# fire_alarm.net
KiCad netlist of a schematic drawn in EAGLE
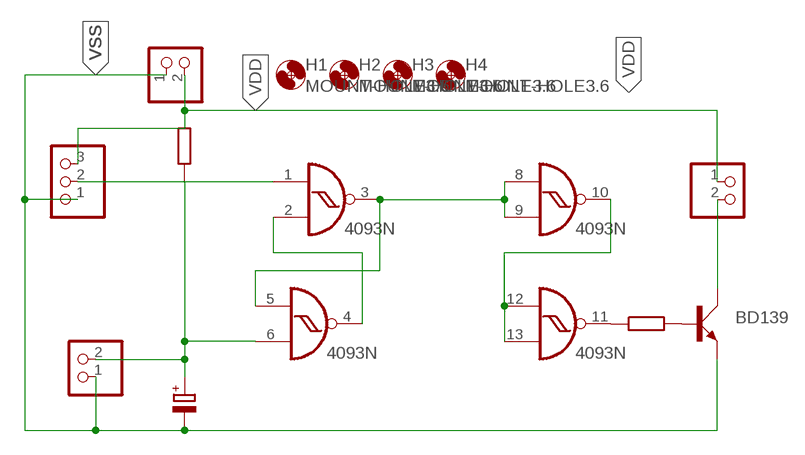
[diagram p0: schematic, sheet 1]

(export (version "E")
  (design (tool "Eeschema 10.0.6"))
  (components
    (comp (ref "C1")
      (value "CPOL-EUE2.5-5")
      (footprint "eagle-import:E2,5-5")
      (libsource (lib "eagle-import") (part "CPOL-EUE2.5-5"))
    )
    (comp (ref "H1")
      (value "MOUNT-HOLE3.6")
      (footprint "eagle-import:3,6")
      (libsource (lib "eagle-import") (part "MOUNT-HOLE3.6"))
    )
    (comp (ref "H2")
      (value "MOUNT-HOLE3.6")
      (footprint "eagle-import:3,6")
      (libsource (lib "eagle-import") (part "MOUNT-HOLE3.6"))
    )
    (comp (ref "H3")
      (value "MOUNT-HOLE3.6")
      (footprint "eagle-import:3,6")
      (libsource (lib "eagle-import") (part "MOUNT-HOLE3.6"))
    )
    (comp (ref "H4")
      (value "MOUNT-HOLE3.6")
      (footprint "eagle-import:3,6")
      (libsource (lib "eagle-import") (part "MOUNT-HOLE3.6"))
    )
    (comp (ref "IC1")
      (value "4093N")
      (footprint "eagle-import:DIL14")
      (libsource (lib "eagle-import") (part "4093N"))
    )
    (comp (ref "JP1")
      (value "PINHD-1X2")
      (footprint "eagle-import:1X02")
      (libsource (lib "eagle-import") (part "PINHD-1X2"))
    )
    (comp (ref "JP2")
      (value "PINHD-1X2")
      (footprint "eagle-import:1X02")
      (libsource (lib "eagle-import") (part "PINHD-1X2"))
    )
    (comp (ref "JP3")
      (value "PINHD-1X2")
      (footprint "eagle-import:1X02")
      (libsource (lib "eagle-import") (part "PINHD-1X2"))
    )
    (comp (ref "JP4")
      (value "PINHD-1X3")
      (footprint "eagle-import:1X03")
      (libsource (lib "eagle-import") (part "PINHD-1X3"))
    )
    (comp (ref "Q1")
      (value "BD139")
      (footprint "eagle-import:TO126AV")
      (libsource (lib "eagle-import") (part "BD139"))
    )
    (comp (ref "R1")
      (value "R-EU_0207/15")
      (footprint "eagle-import:0207_15")
      (libsource (lib "eagle-import") (part "R-EU_0207/15"))
    )
    (comp (ref "R2")
      (value "R-EU_0207/15")
      (footprint "eagle-import:0207_15")
      (libsource (lib "eagle-import") (part "R-EU_0207/15"))
    )
  )
  (nets
    (net (code "1") (name "Net-(IC1A-I0)") (class "Default")
      (node (ref "IC1") (pin "1") (pinfunction "I0_1") (pintype "input"))
      (node (ref "JP4") (pin "2") (pinfunction "2_2") (pintype "passive"))
    )
    (net (code "2") (name "Net-(IC1A-I1)") (class "Default")
      (node (ref "IC1") (pin "2") (pinfunction "I1_2") (pintype "input"))
      (node (ref "IC1") (pin "4") (pinfunction "O_4") (pintype "output"))
    )
    (net (code "3") (name "Net-(IC1A-O)") (class "Default")
      (node (ref "IC1") (pin "3") (pinfunction "O_3") (pintype "output"))
      (node (ref "IC1") (pin "5") (pinfunction "I0_5") (pintype "input"))
      (node (ref "IC1") (pin "8") (pinfunction "I0_8") (pintype "input"))
      (node (ref "IC1") (pin "9") (pinfunction "I1_9") (pintype "input"))
    )
    (net (code "4") (name "Net-(IC1B-I1)") (class "Default")
      (node (ref "C1") (pin "+") (pinfunction "+_+") (pintype "passive"))
      (node (ref "IC1") (pin "6") (pinfunction "I1_6") (pintype "input"))
      (node (ref "JP2") (pin "2") (pinfunction "2_2") (pintype "passive"))
      (node (ref "R2") (pin "1") (pinfunction "1_1") (pintype "passive"))
    )
    (net (code "5") (name "Net-(IC1C-O)") (class "Default")
      (node (ref "IC1") (pin "10") (pinfunction "O_10") (pintype "output"))
      (node (ref "IC1") (pin "12") (pinfunction "I0_12") (pintype "input"))
      (node (ref "IC1") (pin "13") (pinfunction "I1_13") (pintype "input"))
    )
    (net (code "6") (name "Net-(IC1D-O)") (class "Default")
      (node (ref "IC1") (pin "11") (pinfunction "O_11") (pintype "output"))
      (node (ref "R1") (pin "1") (pinfunction "1_1") (pintype "passive"))
    )
    (net (code "7") (name "Net-(JP3-Pad2)") (class "Default")
      (node (ref "JP3") (pin "2") (pinfunction "2_2") (pintype "passive"))
      (node (ref "Q1") (pin "C") (pinfunction "C_C") (pintype "passive"))
    )
    (net (code "8") (name "Net-(Q1-PadB)") (class "Default")
      (node (ref "Q1") (pin "B") (pinfunction "B_B") (pintype "passive"))
      (node (ref "R1") (pin "2") (pinfunction "2_2") (pintype "passive"))
    )
    (net (code "9") (name "VDD") (class "Default")
      (node (ref "JP1") (pin "2") (pinfunction "2_2") (pintype "passive"))
      (node (ref "JP3") (pin "1") (pinfunction "1_1") (pintype "passive"))
      (node (ref "JP4") (pin "3") (pinfunction "3_3") (pintype "passive"))
      (node (ref "R2") (pin "2") (pinfunction "2_2") (pintype "passive"))
    )
    (net (code "10") (name "VSS") (class "Default")
      (node (ref "C1") (pin "-") (pinfunction "-_-") (pintype "passive"))
      (node (ref "JP1") (pin "1") (pinfunction "1_1") (pintype "passive"))
      (node (ref "JP2") (pin "1") (pinfunction "1_1") (pintype "passive"))
      (node (ref "JP4") (pin "1") (pinfunction "1_1") (pintype "passive"))
      (node (ref "Q1") (pin "E") (pinfunction "E_E") (pintype "passive"))
    )
  )
)
